# c12666afe.net
KiCad netlist of a schematic drawn in EAGLE
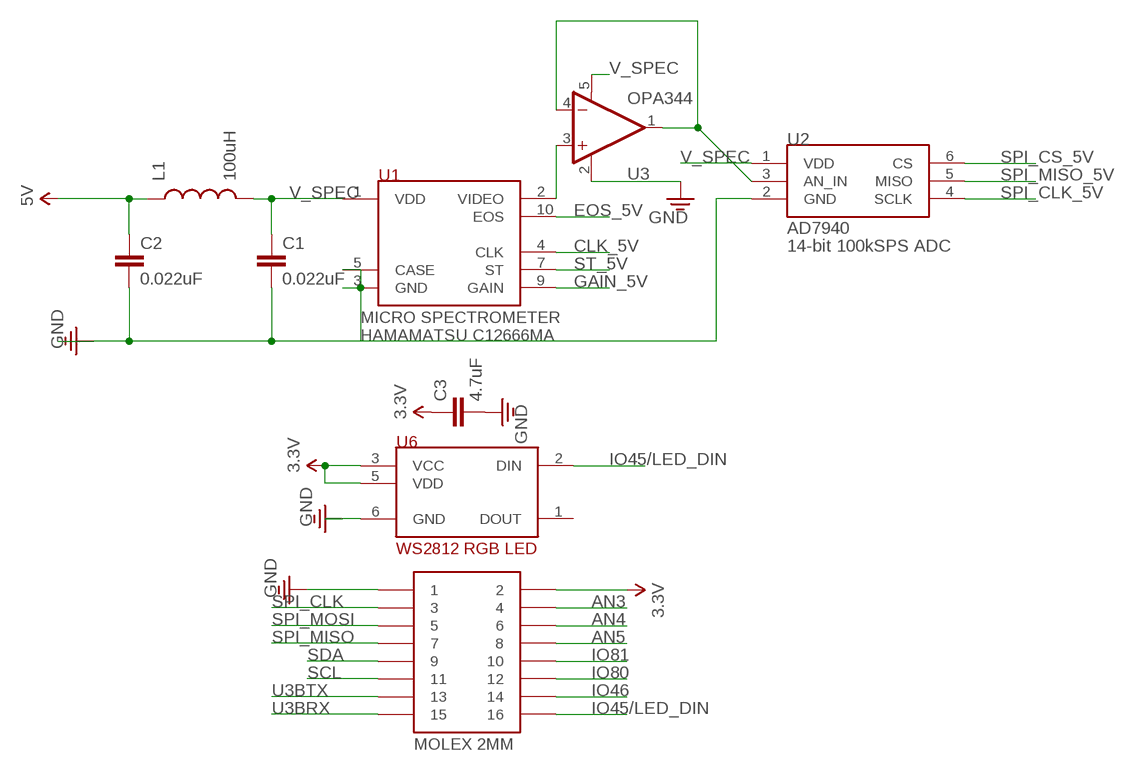
[diagram p0: schematic, sheet 1]

(export (version "E")
  (design (tool "Eeschema 10.0.6"))
  (components
    (comp (ref "2MMCONNECTOR")
      (value "CON-MOLEX-2MMMALE")
      (footprint "eagle-import:MOLEX-0877591650")
      (libsource (lib "eagle-import") (part "CON-MOLEX-2MMMALE"))
    )
    (comp (ref "C1")
      (value "0.022uF")
      (footprint "eagle-import:0603")
      (libsource (lib "eagle-import") (part "CAP0603"))
    )
    (comp (ref "C2")
      (value "0.022uF")
      (footprint "eagle-import:0603")
      (libsource (lib "eagle-import") (part "CAP0603"))
    )
    (comp (ref "C3")
      (value "4.7uF")
      (footprint "eagle-import:0603")
      (libsource (lib "eagle-import") (part "notes_mark5a_CAP0603"))
    )
    (comp (ref "L1")
      (value "100uH")
      (footprint "eagle-import:0805")
      (libsource (lib "eagle-import") (part "INDUCTOR0805"))
    )
    (comp (ref "U1")
      (value "MICROSPEC-C12666MA")
      (footprint "eagle-import:C12666MA")
      (libsource (lib "eagle-import") (part "MICROSPEC-C12666MA"))
    )
    (comp (ref "U2")
      (value "AD7940")
      (footprint "eagle-import:SOT-23-6L")
      (libsource (lib "eagle-import") (part "AD7940"))
    )
    (comp (ref "U3")
      (value "OPA344")
      (footprint "eagle-import:SOT23-5")
      (libsource (lib "eagle-import") (part "OPA344"))
    )
    (comp (ref "U6")
      (value "WS2812_NEOPIXEL")
      (footprint "eagle-import:WS2812")
      (libsource (lib "eagle-import") (part "WS2812_NEOPIXEL"))
    )
  )
  (nets
    (net (code "1") (name "/AN3") (class "Default")
      (node (ref "2MMCONNECTOR") (pin "4") (pinfunction "4_4") (pintype "bidirectional"))
    )
    (net (code "2") (name "/AN4") (class "Default")
      (node (ref "2MMCONNECTOR") (pin "6") (pinfunction "6_6") (pintype "bidirectional"))
    )
    (net (code "3") (name "/AN5") (class "Default")
      (node (ref "2MMCONNECTOR") (pin "8") (pinfunction "8_8") (pintype "bidirectional"))
    )
    (net (code "4") (name "/CLK_5V") (class "Default")
      (node (ref "U1") (pin "4") (pinfunction "CLK_4") (pintype "bidirectional"))
    )
    (net (code "5") (name "/EOS_5V") (class "Default")
      (node (ref "U1") (pin "10") (pinfunction "EOS_10") (pintype "bidirectional"))
    )
    (net (code "6") (name "/GAIN_5V") (class "Default")
      (node (ref "U1") (pin "9") (pinfunction "GAIN_9") (pintype "bidirectional"))
    )
    (net (code "7") (name "/IO45{slash}LED_DIN") (class "Default")
      (node (ref "2MMCONNECTOR") (pin "16") (pinfunction "16_16") (pintype "bidirectional"))
      (node (ref "U6") (pin "2") (pinfunction "DIN_2") (pintype "bidirectional"))
    )
    (net (code "8") (name "/IO46") (class "Default")
      (node (ref "2MMCONNECTOR") (pin "14") (pinfunction "14_14") (pintype "bidirectional"))
    )
    (net (code "9") (name "/IO80") (class "Default")
      (node (ref "2MMCONNECTOR") (pin "12") (pinfunction "12_12") (pintype "bidirectional"))
    )
    (net (code "10") (name "/IO81") (class "Default")
      (node (ref "2MMCONNECTOR") (pin "10") (pinfunction "10_10") (pintype "bidirectional"))
    )
    (net (code "11") (name "/SCL") (class "Default")
      (node (ref "2MMCONNECTOR") (pin "11") (pinfunction "11_11") (pintype "bidirectional"))
    )
    (net (code "12") (name "/SDA") (class "Default")
      (node (ref "2MMCONNECTOR") (pin "9") (pinfunction "9_9") (pintype "bidirectional"))
    )
    (net (code "13") (name "/SPI_CLK") (class "Default")
      (node (ref "2MMCONNECTOR") (pin "3") (pinfunction "3_3") (pintype "bidirectional"))
    )
    (net (code "14") (name "/SPI_CLK_5V") (class "Default")
      (node (ref "U2") (pin "4") (pinfunction "SCLK_4") (pintype "bidirectional"))
    )
    (net (code "15") (name "/SPI_CS_5V") (class "Default")
      (node (ref "U2") (pin "6") (pinfunction "CS_6") (pintype "bidirectional"))
    )
    (net (code "16") (name "/SPI_MISO") (class "Default")
      (node (ref "2MMCONNECTOR") (pin "7") (pinfunction "7_7") (pintype "bidirectional"))
    )
    (net (code "17") (name "/SPI_MISO_5V") (class "Default")
      (node (ref "U2") (pin "5") (pinfunction "MISO_5") (pintype "bidirectional"))
    )
    (net (code "18") (name "/SPI_MOSI") (class "Default")
      (node (ref "2MMCONNECTOR") (pin "5") (pinfunction "5_5") (pintype "bidirectional"))
    )
    (net (code "19") (name "/ST_5V") (class "Default")
      (node (ref "U1") (pin "7") (pinfunction "ST_7") (pintype "bidirectional"))
    )
    (net (code "20") (name "/U3BRX") (class "Default")
      (node (ref "2MMCONNECTOR") (pin "15") (pinfunction "15_15") (pintype "bidirectional"))
    )
    (net (code "21") (name "/U3BTX") (class "Default")
      (node (ref "2MMCONNECTOR") (pin "13") (pinfunction "13_13") (pintype "bidirectional"))
    )
    (net (code "22") (name "/V_SPEC") (class "Default")
      (node (ref "C1") (pin "1") (pinfunction "1_1") (pintype "passive"))
      (node (ref "L1") (pin "2") (pinfunction "2_2") (pintype "passive"))
      (node (ref "U1") (pin "1") (pinfunction "VDD_1") (pintype "bidirectional"))
      (node (ref "U2") (pin "1") (pinfunction "VDD_1") (pintype "bidirectional"))
      (node (ref "U3") (pin "5") (pinfunction "V+_5") (pintype "power_in"))
    )
    (net (code "23") (name "3.3V") (class "Default")
      (node (ref "2MMCONNECTOR") (pin "2") (pinfunction "2_2") (pintype "bidirectional"))
      (node (ref "C3") (pin "1") (pinfunction "1_1") (pintype "passive"))
      (node (ref "U6") (pin "3") (pinfunction "VCC_3") (pintype "bidirectional"))
      (node (ref "U6") (pin "5") (pinfunction "VDD_5") (pintype "bidirectional"))
    )
    (net (code "24") (name "5V") (class "Default")
      (node (ref "C2") (pin "1") (pinfunction "1_1") (pintype "passive"))
      (node (ref "L1") (pin "1") (pinfunction "1_1") (pintype "passive"))
    )
    (net (code "25") (name "GND") (class "Default")
      (node (ref "2MMCONNECTOR") (pin "1") (pinfunction "1_1") (pintype "bidirectional"))
      (node (ref "C1") (pin "2") (pinfunction "2_2") (pintype "passive"))
      (node (ref "C2") (pin "2") (pinfunction "2_2") (pintype "passive"))
      (node (ref "C3") (pin "2") (pinfunction "2_2") (pintype "passive"))
      (node (ref "U1") (pin "3") (pinfunction "GND_3") (pintype "bidirectional"))
      (node (ref "U1") (pin "5") (pinfunction "CASE_5") (pintype "bidirectional"))
      (node (ref "U2") (pin "2") (pinfunction "GND_2") (pintype "bidirectional"))
      (node (ref "U3") (pin "2") (pinfunction "V-_2") (pintype "power_in"))
      (node (ref "U6") (pin "6") (pinfunction "GND_6") (pintype "bidirectional"))
    )
    (net (code "26") (name "Net-(U1-VIDEO)") (class "Default")
      (node (ref "U1") (pin "2") (pinfunction "VIDEO_2") (pintype "bidirectional"))
      (node (ref "U3") (pin "3") (pinfunction "+IN_3") (pintype "input"))
    )
    (net (code "27") (name "Net-(U2-AN_IN)") (class "Default")
      (node (ref "U2") (pin "3") (pinfunction "AN_IN_3") (pintype "bidirectional"))
      (node (ref "U3") (pin "1") (pinfunction "OUT_1") (pintype "output"))
      (node (ref "U3") (pin "4") (pinfunction "-IN_4") (pintype "input"))
    )
    (net (code "28") (name "unconnected-(U6-DOUT-Pad1)") (class "Default")
      (node (ref "U6") (pin "1") (pinfunction "DOUT_1") (pintype "bidirectional"))
    )
  )
)
